# 03_MCU.net
KiCad netlist of a schematic drawn in Altium Designer
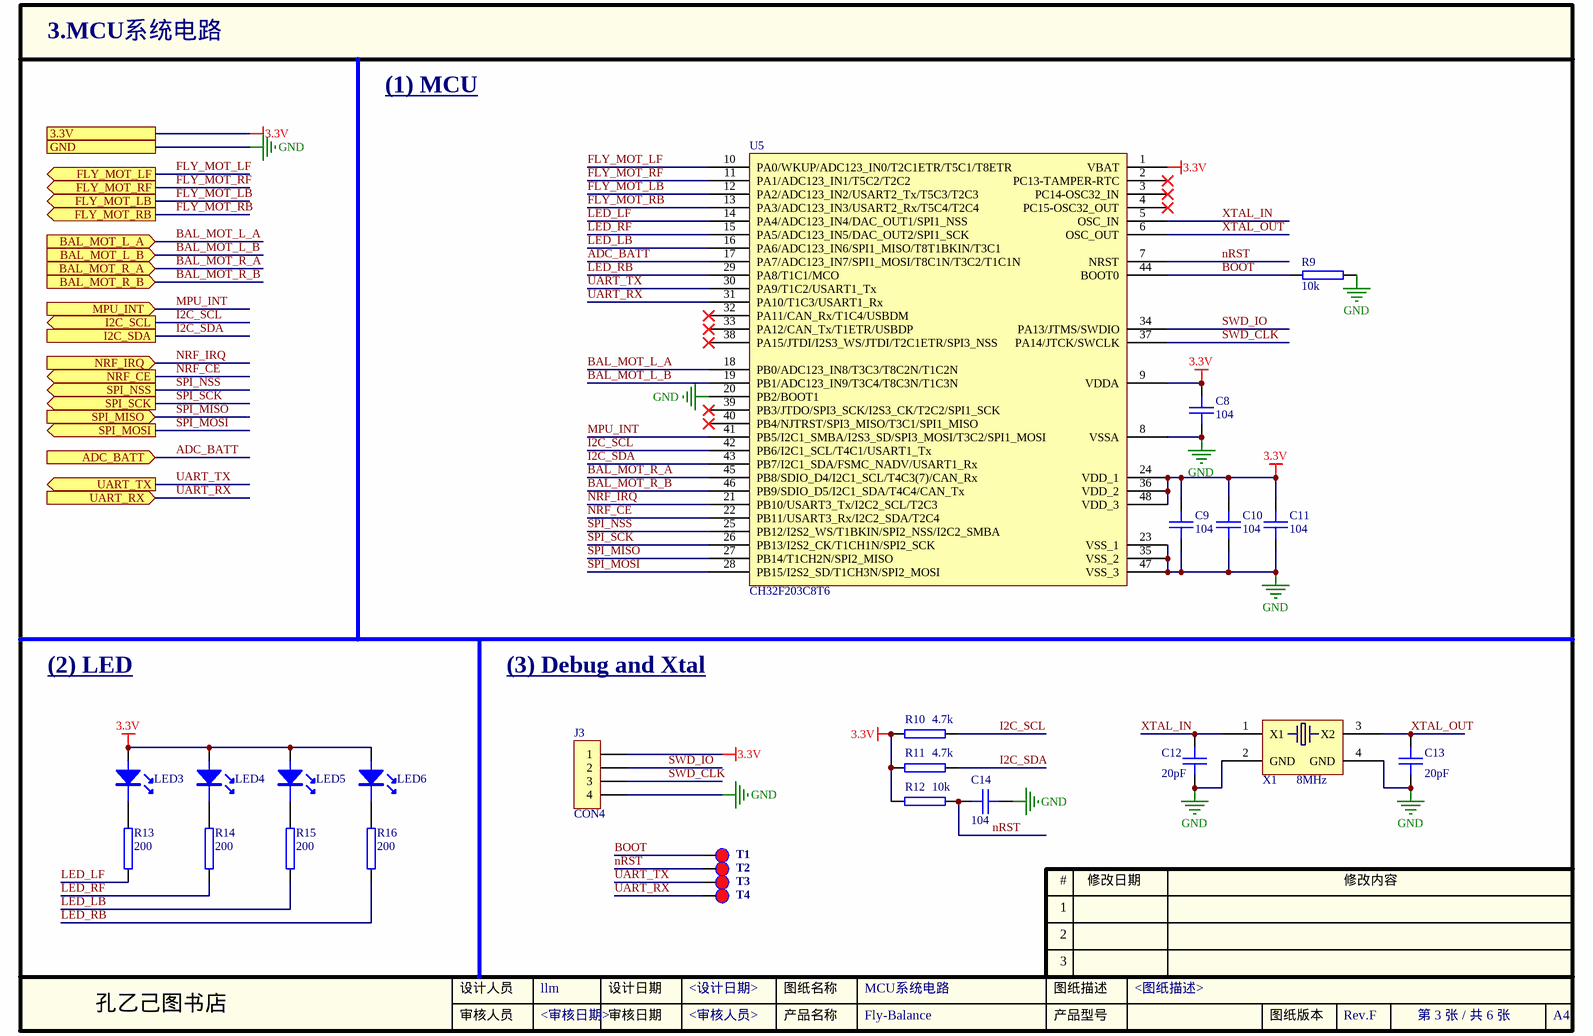
[diagram p0: 03_MCU.SchDoc]

(export (version "E")
  (design (tool "Eeschema 10.0.6"))
  (components
    (comp (ref "C8")
      (value "104")
      (footprint "0402C")
      (description "电容")
      (libsource (lib "MY_Schlib") (part "CAP"))
    )
    (comp (ref "C9")
      (value "104")
      (footprint "0402C")
      (description "电容")
      (libsource (lib "MY_Schlib") (part "CAP"))
    )
    (comp (ref "C10")
      (value "104")
      (footprint "0402C")
      (description "电容")
      (libsource (lib "MY_Schlib") (part "CAP"))
    )
    (comp (ref "C11")
      (value "104")
      (footprint "0402C")
      (description "电容")
      (libsource (lib "MY_Schlib") (part "CAP"))
    )
    (comp (ref "C12")
      (value "20pF")
      (footprint "0402C")
      (description "电容")
      (libsource (lib "MY_Schlib") (part "CAP"))
    )
    (comp (ref "C13")
      (value "20pF")
      (footprint "0402C")
      (description "电容")
      (libsource (lib "MY_Schlib") (part "CAP"))
    )
    (comp (ref "C14")
      (value "104")
      (footprint "0402C")
      (description "电容")
      (libsource (lib "MY_Schlib") (part "CAP"))
    )
    (comp (ref "J3")
      (value "CON4")
      (footprint "SIP-4-2.54")
      (description "Connector")
      (libsource (lib "MY_Schlib") (part "CON4"))
    )
    (comp (ref "LED3")
      (value "Blue")
      (footprint "LED-0603")
      (description "发光二极管")
      (libsource (lib "MY_Schlib") (part "LED"))
    )
    (comp (ref "LED4")
      (value "Blue")
      (footprint "LED-0603")
      (description "发光二极管")
      (libsource (lib "MY_Schlib") (part "LED"))
    )
    (comp (ref "LED5")
      (value "Blue")
      (footprint "LED-0603")
      (description "发光二极管")
      (libsource (lib "MY_Schlib") (part "LED"))
    )
    (comp (ref "LED6")
      (value "Blue")
      (footprint "LED-0603")
      (description "发光二极管")
      (libsource (lib "MY_Schlib") (part "LED"))
    )
    (comp (ref "R9")
      (value "10k")
      (footprint "0402R")
      (description "电阻")
      (libsource (lib "MY_Schlib") (part "RES"))
    )
    (comp (ref "R10")
      (value "4.7k")
      (footprint "0402R")
      (description "电阻")
      (libsource (lib "MY_Schlib") (part "RES"))
    )
    (comp (ref "R11")
      (value "4.7k")
      (footprint "0402R")
      (description "电阻")
      (libsource (lib "MY_Schlib") (part "RES"))
    )
    (comp (ref "R12")
      (value "10k")
      (footprint "0402R")
      (description "电阻")
      (libsource (lib "MY_Schlib") (part "RES"))
    )
    (comp (ref "R13")
      (value "200")
      (footprint "0402R")
      (description "电阻")
      (libsource (lib "MY_Schlib") (part "RES"))
    )
    (comp (ref "R14")
      (value "200")
      (footprint "0402R")
      (description "电阻")
      (libsource (lib "MY_Schlib") (part "RES"))
    )
    (comp (ref "R15")
      (value "200")
      (footprint "0402R")
      (description "电阻")
      (libsource (lib "MY_Schlib") (part "RES"))
    )
    (comp (ref "R16")
      (value "200")
      (footprint "0402R")
      (description "电阻")
      (libsource (lib "MY_Schlib") (part "RES"))
    )
    (comp (ref "T1")
      (value "BOOT")
      (footprint "PAD-40")
      (description "测试点")
      (libsource (lib "MY_Schlib") (part "TEST-DOT"))
    )
    (comp (ref "T2")
      (value "RST")
      (footprint "PAD-40")
      (description "测试点")
      (libsource (lib "MY_Schlib") (part "TEST-DOT"))
    )
    (comp (ref "T3")
      (value "Tx")
      (footprint "PAD-40")
      (description "测试点")
      (libsource (lib "MY_Schlib") (part "TEST-DOT"))
    )
    (comp (ref "T4")
      (value "Rx")
      (footprint "PAD-40")
      (description "测试点")
      (libsource (lib "MY_Schlib") (part "TEST-DOT"))
    )
    (comp (ref "U5")
      (value "CH32F203C8T6")
      (footprint "LQFP-48_7x7")
      (description "STM32单片机48引脚")
      (libsource (lib "MY_Schlib") (part "STM32F103C"))
    )
    (comp (ref "X1")
      (value "8MHz")
      (footprint "OSCCC250X320X80-4N")
      (description "4pin贴片无源晶振")
      (libsource (lib "MY_Schlib") (part "XTAL4"))
    )
  )
  (nets
    (net (code "1") (name "/ADC_BATT") (class "Default")
      (node (ref "U5") (pin "17") (pinfunction "PA7/ADC123_IN7/SPI1_MOSI/T8C1N/T3C2/T1C1N_17") (pintype "passive"))
    )
    (net (code "2") (name "/BAL_MOT_L_A") (class "Default")
      (node (ref "U5") (pin "18") (pinfunction "PB0/ADC123_IN8/T3C3/T8C2N/T1C2N_18") (pintype "passive"))
    )
    (net (code "3") (name "/BAL_MOT_L_B") (class "Default")
      (node (ref "U5") (pin "19") (pinfunction "PB1/ADC123_IN9/T3C4/T8C3N/T1C3N_19") (pintype "passive"))
    )
    (net (code "4") (name "/BAL_MOT_R_A") (class "Default")
      (node (ref "U5") (pin "45") (pinfunction "PB8/SDIO_D4/I2C1_SCL/T4C3(7)/CAN_Rx_45") (pintype "passive"))
    )
    (net (code "5") (name "/BAL_MOT_R_B") (class "Default")
      (node (ref "U5") (pin "46") (pinfunction "PB9/SDIO_D5/I2C1_SDA/T4C4/CAN_Tx_46") (pintype "passive"))
    )
    (net (code "6") (name "/BOOT") (class "Default")
      (node (ref "R9") (pin "1") (pinfunction "1_1") (pintype "passive"))
      (node (ref "T1") (pin "1") (pinfunction "1_1") (pintype "passive"))
      (node (ref "U5") (pin "44") (pinfunction "BOOT0_44") (pintype "passive"))
    )
    (net (code "7") (name "/FLY_MOT_LB") (class "Default")
      (node (ref "U5") (pin "12") (pinfunction "PA2/ADC123_IN2/USART2_Tx/T5C3/T2C3_12") (pintype "passive"))
    )
    (net (code "8") (name "/FLY_MOT_LF") (class "Default")
      (node (ref "U5") (pin "10") (pinfunction "PA0/WKUP/ADC123_IN0/T2C1ETR/T5C1/T8ETR_10") (pintype "passive"))
    )
    (net (code "9") (name "/FLY_MOT_RB") (class "Default")
      (node (ref "U5") (pin "13") (pinfunction "PA3/ADC123_IN3/USART2_Rx/T5C4/T2C4_13") (pintype "passive"))
    )
    (net (code "10") (name "/FLY_MOT_RF") (class "Default")
      (node (ref "U5") (pin "11") (pinfunction "PA1/ADC123_IN1/T5C2/T2C2_11") (pintype "passive"))
    )
    (net (code "11") (name "/I2C_SCL") (class "Default")
      (node (ref "R10") (pin "1") (pinfunction "1_1") (pintype "passive"))
      (node (ref "U5") (pin "42") (pinfunction "PB6/I2C1_SCL/T4C1/USART1_Tx_42") (pintype "passive"))
    )
    (net (code "12") (name "/I2C_SDA") (class "Default")
      (node (ref "R11") (pin "1") (pinfunction "1_1") (pintype "passive"))
      (node (ref "U5") (pin "43") (pinfunction "PB7/I2C1_SDA/FSMC_NADV/USART1_Rx_43") (pintype "passive"))
    )
    (net (code "13") (name "/LED_LB") (class "Default")
      (node (ref "R15") (pin "1") (pinfunction "1_1") (pintype "passive"))
      (node (ref "U5") (pin "16") (pinfunction "PA6/ADC123_IN6/SPI1_MISO/T8T1BKIN/T3C1_16") (pintype "passive"))
    )
    (net (code "14") (name "/LED_LF") (class "Default")
      (node (ref "R13") (pin "1") (pinfunction "1_1") (pintype "passive"))
      (node (ref "U5") (pin "14") (pinfunction "PA4/ADC123_IN4/DAC_OUT1/SPI1_NSS_14") (pintype "passive"))
    )
    (net (code "15") (name "/LED_RB") (class "Default")
      (node (ref "R16") (pin "1") (pinfunction "1_1") (pintype "passive"))
      (node (ref "U5") (pin "29") (pinfunction "PA8/T1C1/MCO_29") (pintype "passive"))
    )
    (net (code "16") (name "/LED_RF") (class "Default")
      (node (ref "R14") (pin "1") (pinfunction "1_1") (pintype "passive"))
      (node (ref "U5") (pin "15") (pinfunction "PA5/ADC123_IN5/DAC_OUT2/SPI1_SCK_15") (pintype "passive"))
    )
    (net (code "17") (name "/MPU_INT") (class "Default")
      (node (ref "U5") (pin "41") (pinfunction "PB5/I2C1_SMBA/I2S3_SD/SPI3_MOSI/T3C2/SPI1_MOSI_41") (pintype "passive"))
    )
    (net (code "18") (name "/NRF_CE") (class "Default")
      (node (ref "U5") (pin "22") (pinfunction "PB11/USART3_Rx/I2C2_SDA/T2C4_22") (pintype "passive"))
    )
    (net (code "19") (name "/NRF_IRQ") (class "Default")
      (node (ref "U5") (pin "21") (pinfunction "PB10/USART3_Tx/I2C2_SCL/T2C3_21") (pintype "passive"))
    )
    (net (code "20") (name "/SPI_MISO") (class "Default")
      (node (ref "U5") (pin "27") (pinfunction "PB14/T1CH2N/SPI2_MISO_27") (pintype "passive"))
    )
    (net (code "21") (name "/SPI_MOSI") (class "Default")
      (node (ref "U5") (pin "28") (pinfunction "PB15/I2S2_SD/T1CH3N/SPI2_MOSI_28") (pintype "passive"))
    )
    (net (code "22") (name "/SPI_NSS") (class "Default")
      (node (ref "U5") (pin "25") (pinfunction "PB12/I2S2_WS/T1BKIN/SPI2_NSS/I2C2_SMBA_25") (pintype "passive"))
    )
    (net (code "23") (name "/SPI_SCK") (class "Default")
      (node (ref "U5") (pin "26") (pinfunction "PB13/I2S2_CK/T1CH1N/SPI2_SCK_26") (pintype "passive"))
    )
    (net (code "24") (name "/SWD_CLK") (class "Default")
      (node (ref "J3") (pin "3") (pinfunction "3_3") (pintype "passive"))
      (node (ref "U5") (pin "37") (pinfunction "PA14/JTCK/SWCLK_37") (pintype "passive"))
    )
    (net (code "25") (name "/SWD_IO") (class "Default")
      (node (ref "J3") (pin "2") (pinfunction "2_2") (pintype "passive"))
      (node (ref "U5") (pin "34") (pinfunction "PA13/JTMS/SWDIO_34") (pintype "passive"))
    )
    (net (code "26") (name "/UART_RX") (class "Default")
      (node (ref "T4") (pin "1") (pinfunction "1_1") (pintype "passive"))
      (node (ref "U5") (pin "31") (pinfunction "PA10/T1C3/USART1_Rx_31") (pintype "passive"))
    )
    (net (code "27") (name "/UART_TX") (class "Default")
      (node (ref "T3") (pin "1") (pinfunction "1_1") (pintype "passive"))
      (node (ref "U5") (pin "30") (pinfunction "PA9/T1C2/USART1_Tx_30") (pintype "passive"))
    )
    (net (code "28") (name "/XTAL_IN") (class "Default")
      (node (ref "C12") (pin "2") (pinfunction "2_2") (pintype "passive"))
      (node (ref "U5") (pin "5") (pinfunction "OSC_IN_5") (pintype "passive"))
      (node (ref "X1") (pin "1") (pinfunction "X1_1") (pintype "passive"))
    )
    (net (code "29") (name "/XTAL_OUT") (class "Default")
      (node (ref "C13") (pin "2") (pinfunction "2_2") (pintype "passive"))
      (node (ref "U5") (pin "6") (pinfunction "OSC_OUT_6") (pintype "passive"))
      (node (ref "X1") (pin "3") (pinfunction "X2_3") (pintype "passive"))
    )
    (net (code "30") (name "/nRST") (class "Default")
      (node (ref "C14") (pin "2") (pinfunction "2_2") (pintype "passive"))
      (node (ref "R12") (pin "1") (pinfunction "1_1") (pintype "passive"))
      (node (ref "T2") (pin "1") (pinfunction "1_1") (pintype "passive"))
      (node (ref "U5") (pin "7") (pinfunction "NRST_7") (pintype "passive"))
    )
    (net (code "31") (name "3.3V") (class "Default")
      (node (ref "C10") (pin "2") (pinfunction "2_2") (pintype "passive"))
      (node (ref "C11") (pin "2") (pinfunction "2_2") (pintype "passive"))
      (node (ref "C8") (pin "2") (pinfunction "2_2") (pintype "passive"))
      (node (ref "C9") (pin "2") (pinfunction "2_2") (pintype "passive"))
      (node (ref "J3") (pin "1") (pinfunction "1_1") (pintype "passive"))
      (node (ref "LED3") (pin "1") (pinfunction "1_1") (pintype "passive"))
      (node (ref "LED4") (pin "1") (pinfunction "1_1") (pintype "passive"))
      (node (ref "LED5") (pin "1") (pinfunction "1_1") (pintype "passive"))
      (node (ref "LED6") (pin "1") (pinfunction "1_1") (pintype "passive"))
      (node (ref "R10") (pin "2") (pinfunction "2_2") (pintype "passive"))
      (node (ref "R11") (pin "2") (pinfunction "2_2") (pintype "passive"))
      (node (ref "R12") (pin "2") (pinfunction "2_2") (pintype "passive"))
      (node (ref "U5") (pin "1") (pinfunction "VBAT_1") (pintype "passive"))
      (node (ref "U5") (pin "24") (pinfunction "VDD_1_24") (pintype "passive"))
      (node (ref "U5") (pin "36") (pinfunction "VDD_2_36") (pintype "passive"))
      (node (ref "U5") (pin "48") (pinfunction "VDD_3_48") (pintype "passive"))
      (node (ref "U5") (pin "9") (pinfunction "VDDA_9") (pintype "passive"))
    )
    (net (code "32") (name "GND") (class "Default")
      (node (ref "C10") (pin "1") (pinfunction "1_1") (pintype "passive"))
      (node (ref "C11") (pin "1") (pinfunction "1_1") (pintype "passive"))
      (node (ref "C12") (pin "1") (pinfunction "1_1") (pintype "passive"))
      (node (ref "C13") (pin "1") (pinfunction "1_1") (pintype "passive"))
      (node (ref "C14") (pin "1") (pinfunction "1_1") (pintype "passive"))
      (node (ref "C8") (pin "1") (pinfunction "1_1") (pintype "passive"))
      (node (ref "C9") (pin "1") (pinfunction "1_1") (pintype "passive"))
      (node (ref "J3") (pin "4") (pinfunction "4_4") (pintype "passive"))
      (node (ref "R9") (pin "2") (pinfunction "2_2") (pintype "passive"))
      (node (ref "U5") (pin "20") (pinfunction "PB2/BOOT1_20") (pintype "passive"))
      (node (ref "U5") (pin "23") (pinfunction "VSS_1_23") (pintype "passive"))
      (node (ref "U5") (pin "35") (pinfunction "VSS_2_35") (pintype "passive"))
      (node (ref "U5") (pin "47") (pinfunction "VSS_3_47") (pintype "passive"))
      (node (ref "U5") (pin "8") (pinfunction "VSSA_8") (pintype "passive"))
      (node (ref "X1") (pin "2") (pinfunction "GND_2") (pintype "passive"))
      (node (ref "X1") (pin "4") (pinfunction "GND_4") (pintype "passive"))
    )
    (net (code "33") (name "Net-(LED3-Pad2)") (class "Default")
      (node (ref "LED3") (pin "2") (pinfunction "2_2") (pintype "passive"))
      (node (ref "R13") (pin "2") (pinfunction "2_2") (pintype "passive"))
    )
    (net (code "34") (name "Net-(LED4-Pad2)") (class "Default")
      (node (ref "LED4") (pin "2") (pinfunction "2_2") (pintype "passive"))
      (node (ref "R14") (pin "2") (pinfunction "2_2") (pintype "passive"))
    )
    (net (code "35") (name "Net-(LED5-Pad2)") (class "Default")
      (node (ref "LED5") (pin "2") (pinfunction "2_2") (pintype "passive"))
      (node (ref "R15") (pin "2") (pinfunction "2_2") (pintype "passive"))
    )
    (net (code "36") (name "Net-(LED6-Pad2)") (class "Default")
      (node (ref "LED6") (pin "2") (pinfunction "2_2") (pintype "passive"))
      (node (ref "R16") (pin "2") (pinfunction "2_2") (pintype "passive"))
    )
    (net (code "37") (name "unconnected-(U5-PA11{slash}CAN_Rx{slash}T1C4{slash}USBDM-Pad32)") (class "Default")
      (node (ref "U5") (pin "32") (pinfunction "PA11/CAN_Rx/T1C4/USBDM_32") (pintype "passive+no_connect"))
    )
    (net (code "38") (name "unconnected-(U5-PA12{slash}CAN_Tx{slash}T1ETR{slash}USBDP-Pad33)") (class "Default")
      (node (ref "U5") (pin "33") (pinfunction "PA12/CAN_Tx/T1ETR/USBDP_33") (pintype "passive+no_connect"))
    )
    (net (code "39") (name "unconnected-(U5-PA15{slash}JTDI{slash}I2S3_WS{slash}JTDI{slash}T2C1ETR{slash}SPI3_NSS-Pad38)") (class "Default")
      (node (ref "U5") (pin "38") (pinfunction "PA15/JTDI/I2S3_WS/JTDI/T2C1ETR/SPI3_NSS_38") (pintype "passive+no_connect"))
    )
    (net (code "40") (name "unconnected-(U5-PB3{slash}JTDO{slash}SPI3_SCK{slash}I2S3_CK{slash}T2C2{slash}SPI1_SCK-Pad39)") (class "Default")
      (node (ref "U5") (pin "39") (pinfunction "PB3/JTDO/SPI3_SCK/I2S3_CK/T2C2/SPI1_SCK_39") (pintype "passive+no_connect"))
    )
    (net (code "41") (name "unconnected-(U5-PB4{slash}NJTRST{slash}SPI3_MISO{slash}T3C1{slash}SPI1_MISO-Pad40)") (class "Default")
      (node (ref "U5") (pin "40") (pinfunction "PB4/NJTRST/SPI3_MISO/T3C1/SPI1_MISO_40") (pintype "passive+no_connect"))
    )
    (net (code "42") (name "unconnected-(U5-PC13-TAMPER-RTC-Pad2)") (class "Default")
      (node (ref "U5") (pin "2") (pinfunction "PC13-TAMPER-RTC_2") (pintype "passive+no_connect"))
    )
    (net (code "43") (name "unconnected-(U5-PC14-OSC32_IN-Pad3)") (class "Default")
      (node (ref "U5") (pin "3") (pinfunction "PC14-OSC32_IN_3") (pintype "passive+no_connect"))
    )
    (net (code "44") (name "unconnected-(U5-PC15-OSC32_OUT-Pad4)") (class "Default")
      (node (ref "U5") (pin "4") (pinfunction "PC15-OSC32_OUT_4") (pintype "passive+no_connect"))
    )
  )
)
